# RFBoard.net
KiCad netlist of a schematic drawn in Altium Designer
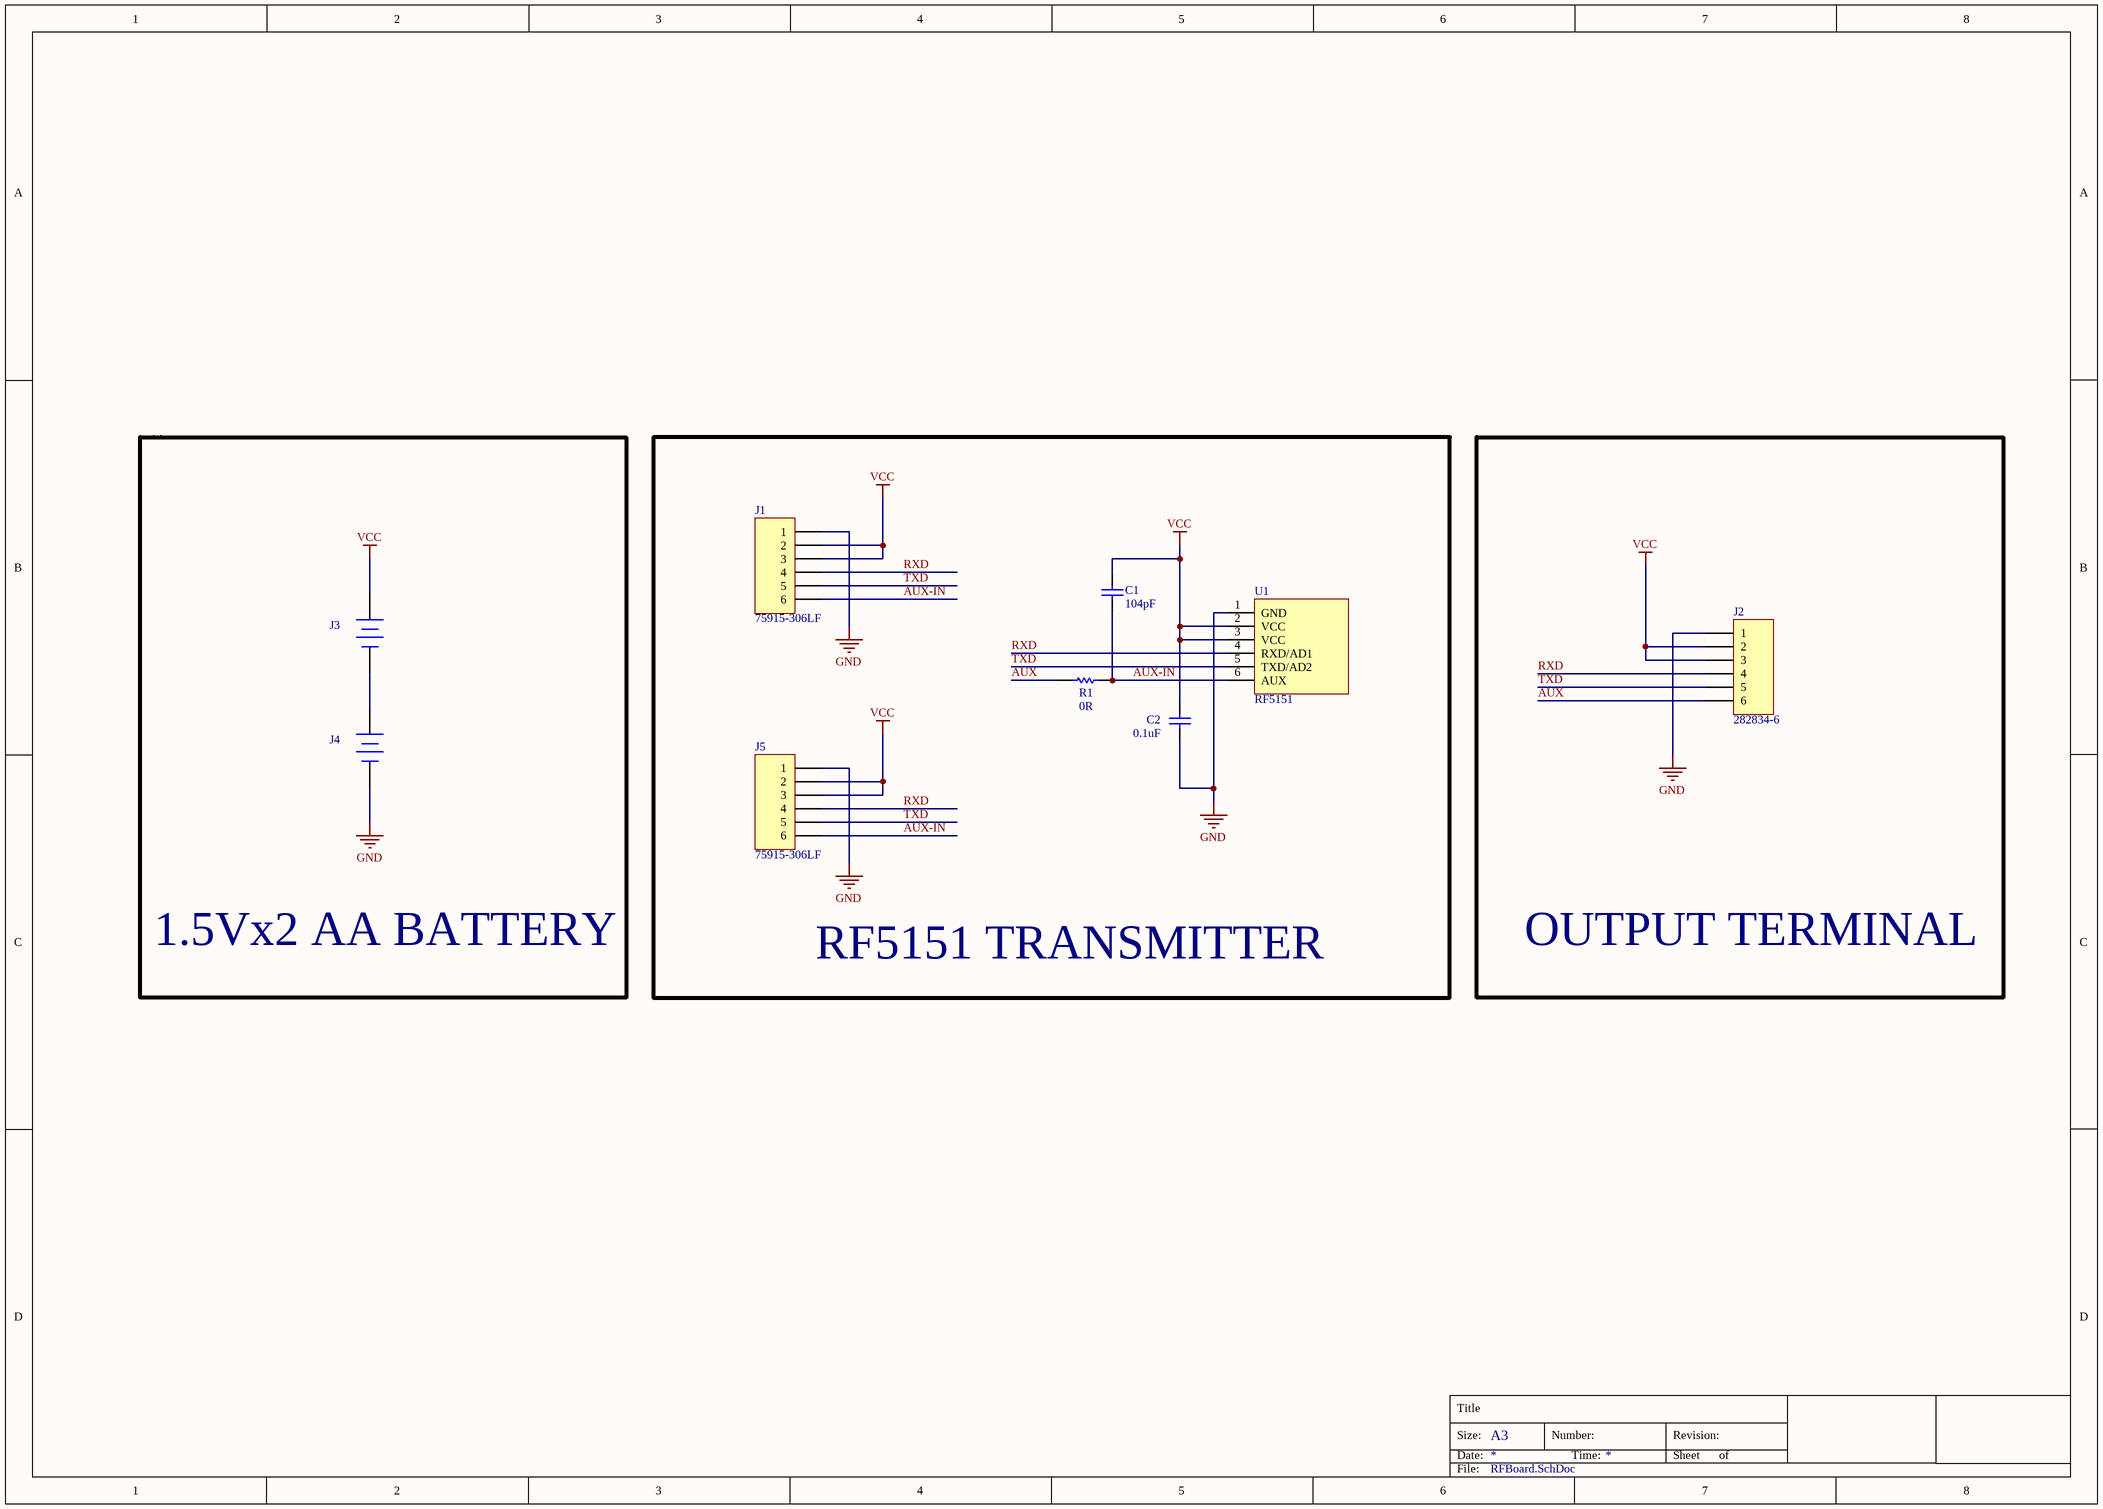
[diagram p0: RFBoard.SchDoc]

(export (version "E")
  (design (tool "Eeschema 10.0.6"))
  (components
    (comp (ref "C1") (value "104pF") (footprint "C1206") (libsource (lib "M9J_RLC") (part "CAP_CERAMIC")))
    (comp (ref "C2") (value "0.1uF") (footprint "C1206") (libsource (lib "M9J_RLC") (part "CAP_CERAMIC")))
    (comp (ref "J1")
      (value "75915-306LF")
      (footprint "HDR1X6_FEMALE-(75915-306LF)")
      (libsource (lib "M9J_Connectors") (part "HDR1X6"))
    )
    (comp (ref "J2")
      (value "282834-6")
      (footprint "TB1X6_P2.54-(282834-6)")
      (libsource (lib "") (part "HDR1X6_1"))
    )
    (comp (ref "J3")
      (value "BATT-2PIN")
      (footprint "BATT-AA-1")
      (libsource (lib "M9J_Connectors") (part "BATT-2PIN"))
    )
    (comp (ref "J4")
      (value "BATT-2PIN")
      (footprint "BATT-AA-1")
      (libsource (lib "M9J_Connectors") (part "BATT-2PIN"))
    )
    (comp (ref "J5")
      (value "75915-306LF")
      (footprint "HDR1X6_FEMALE-(75915-306LF)")
      (libsource (lib "M9J_Connectors") (part "HDR1X6"))
    )
    (comp (ref "R1") (value "0R") (footprint "R1206-SHORT") (libsource (lib "M9J_RLC") (part "RES")))
    (comp (ref "U1") (value "RF5151") (footprint "RF5151") (libsource (lib "M9J_RF") (part "RF5151")))
  )
  (nets
    (net (code "1") (name "/AUX") (class "Default")
      (node (ref "J2") (pin "6") (pinfunction "6_6") (pintype "passive"))
      (node (ref "R1") (pin "1") (pinfunction "1_1") (pintype "passive"))
    )
    (net (code "2") (name "/AUX-IN") (class "Default")
      (node (ref "C1") (pin "1") (pinfunction "1_1") (pintype "passive"))
      (node (ref "J1") (pin "6") (pinfunction "6_6") (pintype "passive"))
      (node (ref "J5") (pin "6") (pinfunction "6_6") (pintype "passive"))
      (node (ref "R1") (pin "2") (pinfunction "2_2") (pintype "passive"))
      (node (ref "U1") (pin "6") (pinfunction "AUX_6") (pintype "passive"))
    )
    (net (code "3") (name "/RXD") (class "Default")
      (node (ref "J1") (pin "4") (pinfunction "4_4") (pintype "passive"))
      (node (ref "J2") (pin "4") (pinfunction "4_4") (pintype "passive"))
      (node (ref "J5") (pin "4") (pinfunction "4_4") (pintype "passive"))
      (node (ref "U1") (pin "4") (pinfunction "RXD/AD1_4") (pintype "passive"))
    )
    (net (code "4") (name "/TXD") (class "Default")
      (node (ref "J1") (pin "5") (pinfunction "5_5") (pintype "passive"))
      (node (ref "J2") (pin "5") (pinfunction "5_5") (pintype "passive"))
      (node (ref "J5") (pin "5") (pinfunction "5_5") (pintype "passive"))
      (node (ref "U1") (pin "5") (pinfunction "TXD/AD2_5") (pintype "passive"))
    )
    (net (code "5") (name "GND") (class "Default")
      (node (ref "C2") (pin "2") (pinfunction "2_2") (pintype "passive"))
      (node (ref "J1") (pin "1") (pinfunction "1_1") (pintype "passive"))
      (node (ref "J2") (pin "1") (pinfunction "1_1") (pintype "passive"))
      (node (ref "J4") (pin "2") (pinfunction "-_2") (pintype "passive"))
      (node (ref "J5") (pin "1") (pinfunction "1_1") (pintype "passive"))
      (node (ref "U1") (pin "1") (pinfunction "GND_1") (pintype "passive"))
    )
    (net (code "6") (name "Net-(J3--)") (class "Default")
      (node (ref "J3") (pin "2") (pinfunction "-_2") (pintype "passive"))
      (node (ref "J4") (pin "1") (pinfunction "+_1") (pintype "passive"))
    )
    (net (code "7") (name "VCC") (class "Default")
      (node (ref "C1") (pin "2") (pinfunction "2_2") (pintype "passive"))
      (node (ref "C2") (pin "1") (pinfunction "1_1") (pintype "passive"))
      (node (ref "J1") (pin "2") (pinfunction "2_2") (pintype "passive"))
      (node (ref "J1") (pin "3") (pinfunction "3_3") (pintype "passive"))
      (node (ref "J2") (pin "2") (pinfunction "2_2") (pintype "passive"))
      (node (ref "J2") (pin "3") (pinfunction "3_3") (pintype "passive"))
      (node (ref "J3") (pin "1") (pinfunction "+_1") (pintype "passive"))
      (node (ref "J5") (pin "2") (pinfunction "2_2") (pintype "passive"))
      (node (ref "J5") (pin "3") (pinfunction "3_3") (pintype "passive"))
      (node (ref "U1") (pin "2") (pinfunction "VCC_2") (pintype "passive"))
      (node (ref "U1") (pin "3") (pinfunction "VCC_3") (pintype "passive"))
    )
  )
)
